# Port_Controller.net
KiCad netlist of a schematic drawn in Altium Designer
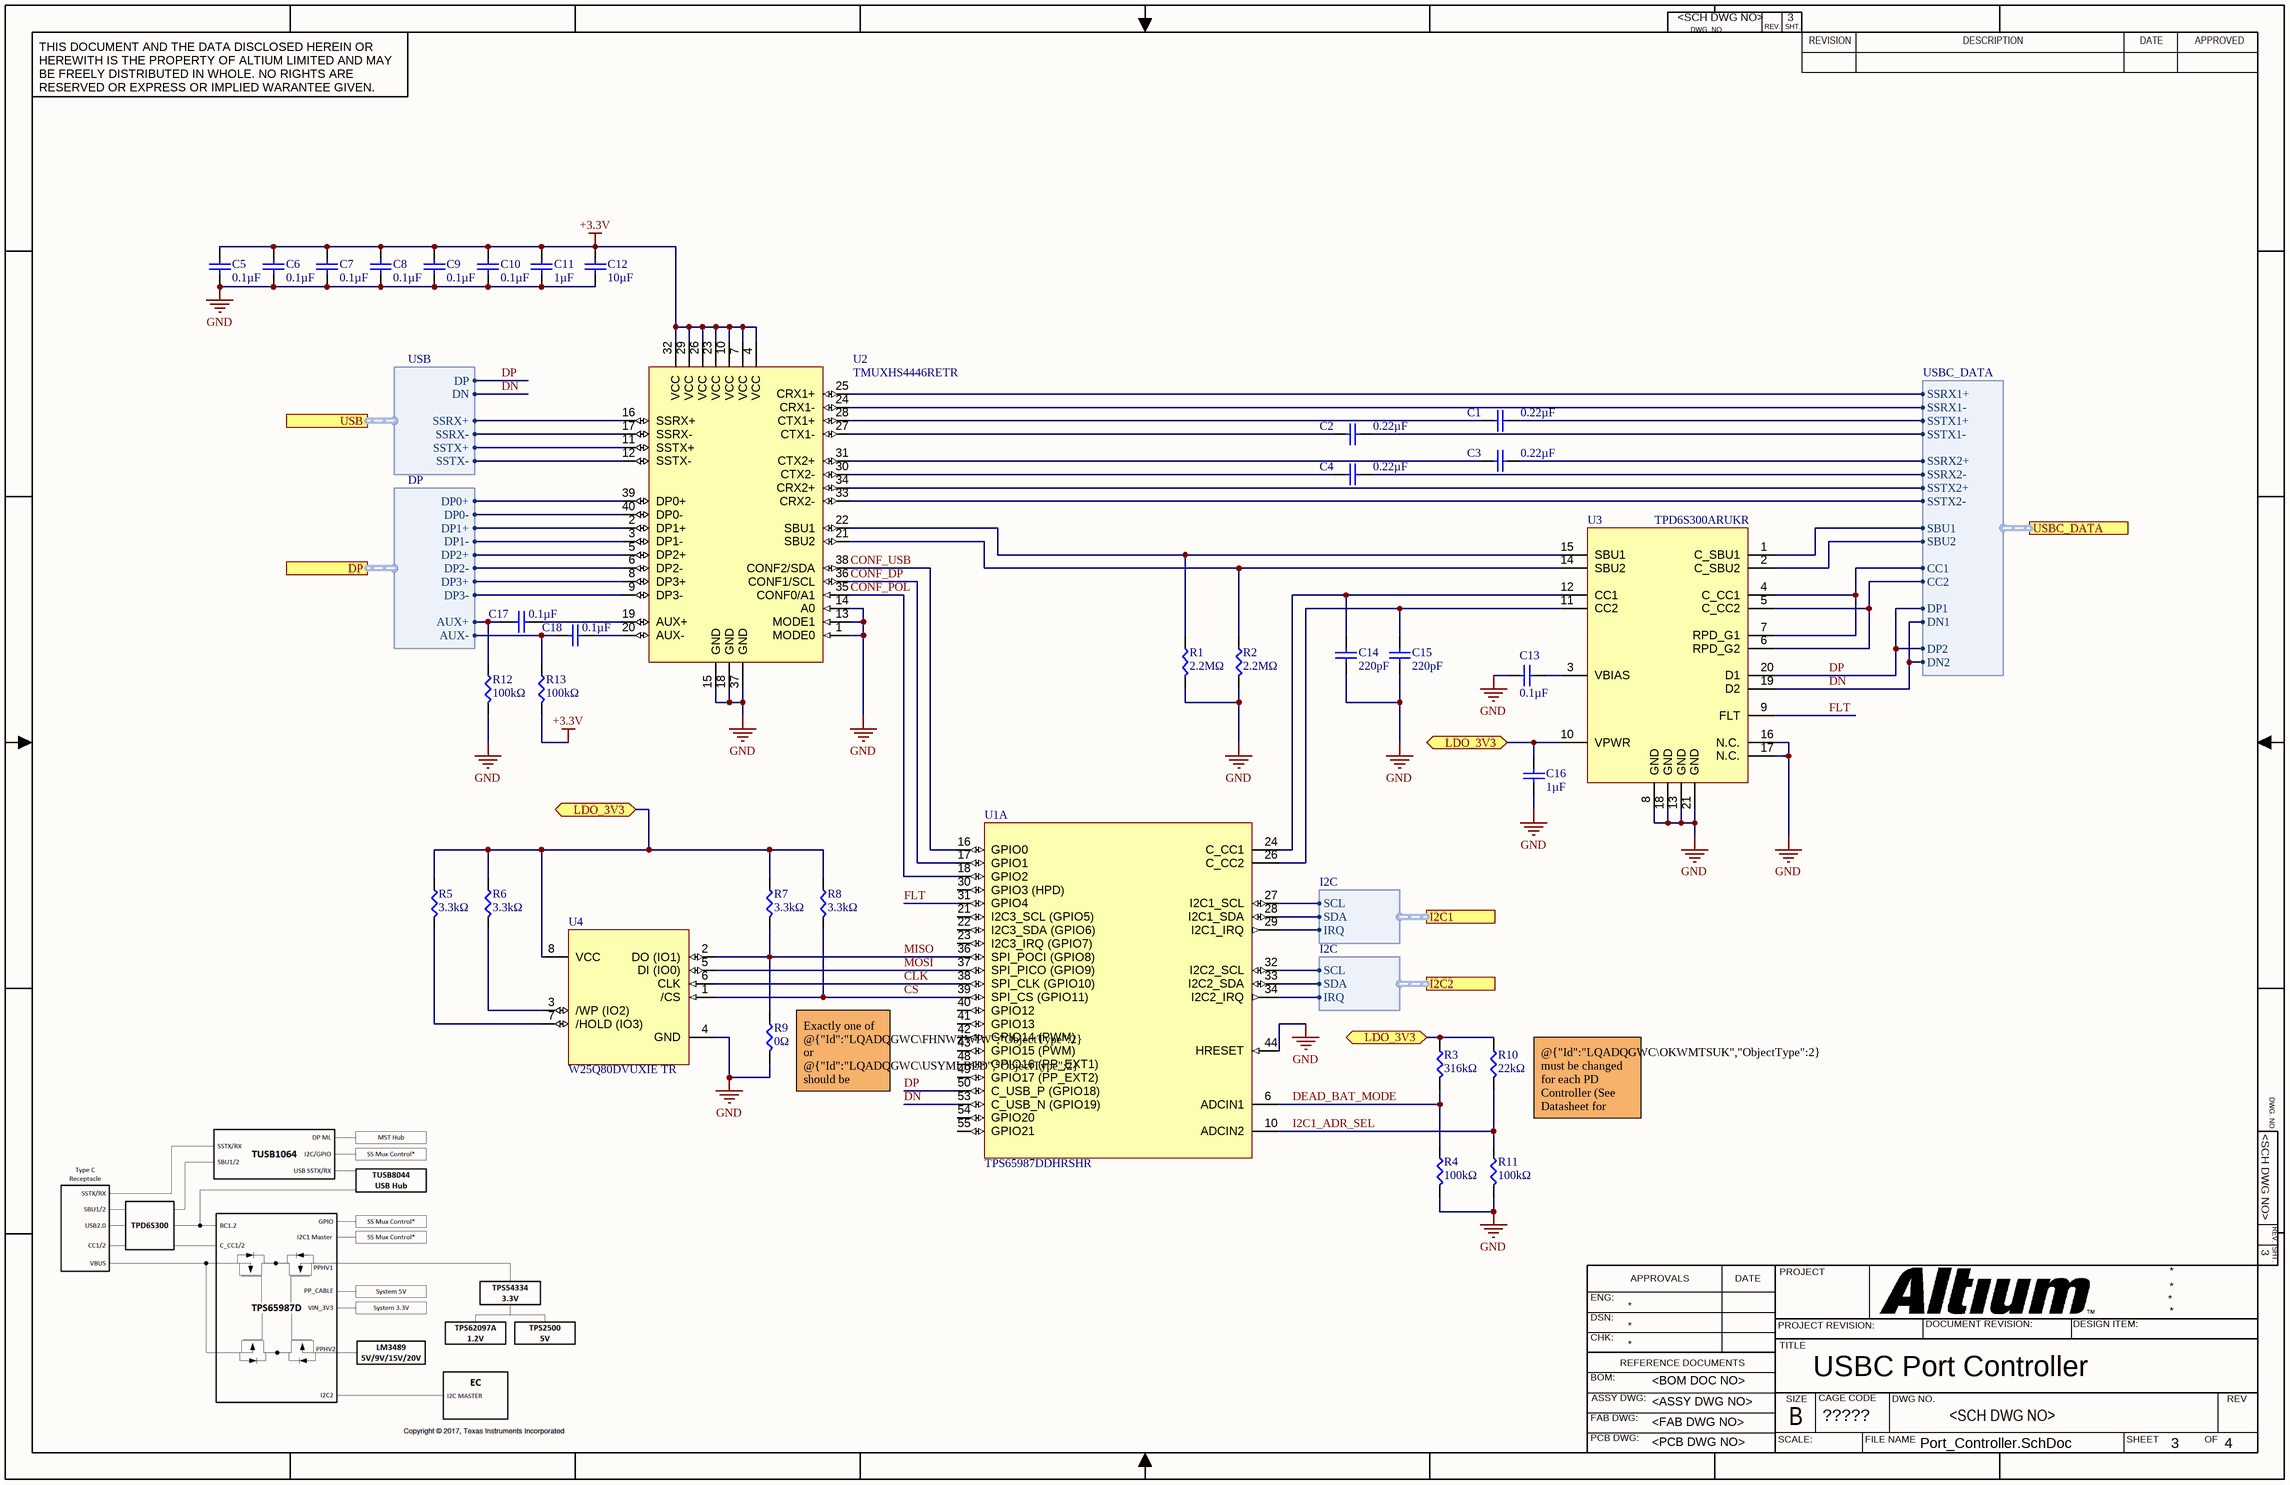
[diagram p0: Port_Controller.SchDoc]

(export (version "E")
  (design (tool "Eeschema 10.0.6"))
  (components
    (comp (ref "C1")
      (value "0.22µF")
      (footprint "CAP0402")
      (description "0.22 µF ±10% 50V Ceramic Capacitor X5R 0402 (1005 Metric)")
      (fields (field (name "VOLTAGE") "50V") (field (name "Comment") "UMK105BJ224KV-F"))
      (libsource (lib "Schlib1") (part "UMK105BJ224KV-F"))
    )
    (comp (ref "C2")
      (value "0.22µF")
      (footprint "CAP0402")
      (description "0.22 µF ±10% 50V Ceramic Capacitor X5R 0402 (1005 Metric)")
      (fields (field (name "VOLTAGE") "50V") (field (name "Comment") "UMK105BJ224KV-F"))
      (libsource (lib "Schlib1") (part "UMK105BJ224KV-F"))
    )
    (comp (ref "C3")
      (value "0.22µF")
      (footprint "CAP0402")
      (description "0.22 µF ±10% 50V Ceramic Capacitor X5R 0402 (1005 Metric)")
      (fields (field (name "VOLTAGE") "50V") (field (name "Comment") "UMK105BJ224KV-F"))
      (libsource (lib "Schlib1") (part "UMK105BJ224KV-F"))
    )
    (comp (ref "C4")
      (value "0.22µF")
      (footprint "CAP0402")
      (description "0.22 µF ±10% 50V Ceramic Capacitor X5R 0402 (1005 Metric)")
      (fields (field (name "VOLTAGE") "50V") (field (name "Comment") "UMK105BJ224KV-F"))
      (libsource (lib "Schlib1") (part "UMK105BJ224KV-F"))
    )
    (comp (ref "C5")
      (value "0.1µF")
      (footprint "CAP0402")
      (description "0.1 µF ±10% 50V Ceramic Capacitor X5R 0402 (1005 Metric)")
      (fields (field (name "VOLTAGE") "50V") (field (name "Comment") "CC0402KRX5R9BB104"))
      (libsource (lib "Schlib1") (part "CC0402KRX5R9BB104"))
    )
    (comp (ref "C6")
      (value "0.1µF")
      (footprint "CAP0402")
      (description "0.1 µF ±10% 50V Ceramic Capacitor X5R 0402 (1005 Metric)")
      (fields (field (name "VOLTAGE") "50V") (field (name "Comment") "CC0402KRX5R9BB104"))
      (libsource (lib "Schlib1") (part "CC0402KRX5R9BB104"))
    )
    (comp (ref "C7")
      (value "0.1µF")
      (footprint "CAP0402")
      (description "0.1 µF ±10% 50V Ceramic Capacitor X5R 0402 (1005 Metric)")
      (fields (field (name "VOLTAGE") "50V") (field (name "Comment") "CC0402KRX5R9BB104"))
      (libsource (lib "Schlib1") (part "CC0402KRX5R9BB104"))
    )
    (comp (ref "C8")
      (value "0.1µF")
      (footprint "CAP0402")
      (description "0.1 µF ±10% 50V Ceramic Capacitor X5R 0402 (1005 Metric)")
      (fields (field (name "VOLTAGE") "50V") (field (name "Comment") "CC0402KRX5R9BB104"))
      (libsource (lib "Schlib1") (part "CC0402KRX5R9BB104"))
    )
    (comp (ref "C9")
      (value "0.1µF")
      (footprint "CAP0402")
      (description "0.1 µF ±10% 50V Ceramic Capacitor X5R 0402 (1005 Metric)")
      (fields (field (name "VOLTAGE") "50V") (field (name "Comment") "CC0402KRX5R9BB104"))
      (libsource (lib "Schlib1") (part "CC0402KRX5R9BB104"))
    )
    (comp (ref "C10")
      (value "0.1µF")
      (footprint "CAP0402")
      (description "0.1 µF ±10% 50V Ceramic Capacitor X5R 0402 (1005 Metric)")
      (fields (field (name "VOLTAGE") "50V") (field (name "Comment") "CC0402KRX5R9BB104"))
      (libsource (lib "Schlib1") (part "CC0402KRX5R9BB104"))
    )
    (comp (ref "C11")
      (value "1µF")
      (footprint "CAP0402")
      (description "1 µF ±10% 16V Ceramic Capacitor X5R 0402 (1005 Metric)")
      (fields (field (name "VOLTAGE") "16V") (field (name "Comment") "CL05A105KO5NNNC"))
      (libsource (lib "Schlib1") (part "CL05A105KO5NNNC"))
    )
    (comp (ref "C12")
      (value "10µF")
      (footprint "CAP0402")
      (description "10 µF ±20% 6.3V Ceramic Capacitor X5R 0402 (1005 Metric)")
      (fields (field (name "VOLTAGE") "6.3V") (field (name "Comment") "CL05A106MQ5NUNC"))
      (libsource (lib "Schlib1") (part "CL05A106MQ5NUNC"))
    )
    (comp (ref "C13")
      (value "0.1µF")
      (footprint "CAP0402")
      (description "0.1 µF ±10% 50V Ceramic Capacitor X5R 0402 (1005 Metric)")
      (fields (field (name "VOLTAGE") "50V") (field (name "Comment") "CC0402KRX5R9BB104"))
      (libsource (lib "Schlib1") (part "CC0402KRX5R9BB104"))
    )
    (comp (ref "C14")
      (value "220pF")
      (footprint "CAP0402")
      (description "220 pF ±5% 50V Ceramic Capacitor C0G, NP0 0402 (1005 Metric)")
      (fields (field (name "VOLTAGE") "50V") (field (name "Comment") "GRM1555C1H221JA01D"))
      (libsource (lib "Schlib1") (part "GRM1555C1H221JA01D"))
    )
    (comp (ref "C15")
      (value "220pF")
      (footprint "CAP0402")
      (description "220 pF ±5% 50V Ceramic Capacitor C0G, NP0 0402 (1005 Metric)")
      (fields (field (name "VOLTAGE") "50V") (field (name "Comment") "GRM1555C1H221JA01D"))
      (libsource (lib "Schlib1") (part "GRM1555C1H221JA01D"))
    )
    (comp (ref "C16")
      (value "1µF")
      (footprint "CAP0402")
      (description "1 µF ±10% 16V Ceramic Capacitor X5R 0402 (1005 Metric)")
      (fields (field (name "VOLTAGE") "16V") (field (name "Comment") "CL05A105KO5NNNC"))
      (libsource (lib "Schlib1") (part "CL05A105KO5NNNC"))
    )
    (comp (ref "C17")
      (value "0.1µF")
      (footprint "CAP0402")
      (description "0.1 µF ±10% 50V Ceramic Capacitor X5R 0402 (1005 Metric)")
      (fields (field (name "VOLTAGE") "50V") (field (name "Comment") "CC0402KRX5R9BB104"))
      (libsource (lib "Schlib1") (part "CC0402KRX5R9BB104"))
    )
    (comp (ref "C18")
      (value "0.1µF")
      (footprint "CAP0402")
      (description "0.1 µF ±10% 50V Ceramic Capacitor X5R 0402 (1005 Metric)")
      (fields (field (name "VOLTAGE") "50V") (field (name "Comment") "CC0402KRX5R9BB104"))
      (libsource (lib "Schlib1") (part "CC0402KRX5R9BB104"))
    )
    (comp (ref "R1")
      (value "2.2MΩ")
      (footprint "RES0402")
      (description "2.2 MOhms ±1% 0.063W, 1/16W Chip Resistor 0402 (1005 Metric) Moisture Resistant Thick Film")
      (fields (field (name "Comment") "RC0402FR-072M2L"))
      (libsource (lib "Schlib1") (part "RC0402FR-072M2L"))
    )
    (comp (ref "R2")
      (value "2.2MΩ")
      (footprint "RES0402")
      (description "2.2 MOhms ±1% 0.063W, 1/16W Chip Resistor 0402 (1005 Metric) Moisture Resistant Thick Film")
      (fields (field (name "Comment") "RC0402FR-072M2L"))
      (libsource (lib "Schlib1") (part "RC0402FR-072M2L"))
    )
    (comp (ref "R3")
      (value "316kΩ")
      (footprint "RES0402")
      (description "316 kOhms ±1% 0.1W, 1/10W Chip Resistor 0402 (1005 Metric) Automotive AEC-Q200 Thick Film")
      (fields (field (name "Comment") "CRCW0402316KFKED"))
      (libsource (lib "Schlib1") (part "CRCW0402316KFKED"))
    )
    (comp (ref "R4")
      (value "100kΩ")
      (footprint "RES0402")
      (description "100 kOhms ±1% 0.1W, 1/10W Chip Resistor 0402 (1005 Metric) Automotive AEC-Q200 Thick Film")
      (fields (field (name "Comment") "ERJ-2RKF1003X"))
      (libsource (lib "Schlib1") (part "ERJ-2RKF1003X"))
    )
    (comp (ref "R5")
      (value "3.3kΩ")
      (footprint "RES0402")
      (description "3.3 kOhms ±0.1% 0.063W, 1/16W Chip Resistor 0402 (1005 Metric) Automotive AEC-Q200 Thin Film")
      (fields (field (name "Comment") "ERA-2AEB332X"))
      (libsource (lib "Schlib1") (part "ERA-2AEB332X"))
    )
    (comp (ref "R6")
      (value "3.3kΩ")
      (footprint "RES0402")
      (description "3.3 kOhms ±0.1% 0.063W, 1/16W Chip Resistor 0402 (1005 Metric) Automotive AEC-Q200 Thin Film")
      (fields (field (name "Comment") "ERA-2AEB332X"))
      (libsource (lib "Schlib1") (part "ERA-2AEB332X"))
    )
    (comp (ref "R7")
      (value "3.3kΩ")
      (footprint "RES0402")
      (description "3.3 kOhms ±0.1% 0.063W, 1/16W Chip Resistor 0402 (1005 Metric) Automotive AEC-Q200 Thin Film")
      (fields (field (name "Comment") "ERA-2AEB332X"))
      (libsource (lib "Schlib1") (part "ERA-2AEB332X"))
    )
    (comp (ref "R8")
      (value "3.3kΩ")
      (footprint "RES0402")
      (description "3.3 kOhms ±0.1% 0.063W, 1/16W Chip Resistor 0402 (1005 Metric) Automotive AEC-Q200 Thin Film")
      (fields (field (name "Comment") "ERA-2AEB332X"))
      (libsource (lib "Schlib1") (part "ERA-2AEB332X"))
    )
    (comp (ref "R9")
      (value "0Ω")
      (footprint "RES0402")
      (description "0 Ohms Jumper Chip Resistor 0402 (1005 Metric) Moisture Resistant Thick Film")
      (fields (field (name "Comment") "RC0402JR-070RL"))
      (libsource (lib "Schlib1") (part "RC0402JR-070RL"))
    )
    (comp (ref "R10")
      (value "22kΩ")
      (footprint "RES0402")
      (description "22 kOhms ±1% 0.1W, 1/10W Chip Resistor 0402 (1005 Metric) Automotive AEC-Q200 Thick Film")
      (fields (field (name "Comment") "ERJ-2RKF2202X"))
      (libsource (lib "Schlib1") (part "ERJ-2RKF2202X"))
    )
    (comp (ref "R11")
      (value "100kΩ")
      (footprint "RES0402")
      (description "100 kOhms ±1% 0.1W, 1/10W Chip Resistor 0402 (1005 Metric) Automotive AEC-Q200 Thick Film")
      (fields (field (name "Comment") "ERJ-2RKF1003X"))
      (libsource (lib "Schlib1") (part "ERJ-2RKF1003X"))
    )
    (comp (ref "R12")
      (value "100kΩ")
      (footprint "RES0402")
      (description "100 kOhms ±1% 0.1W, 1/10W Chip Resistor 0402 (1005 Metric) Automotive AEC-Q200 Thick Film")
      (fields (field (name "Comment") "ERJ-2RKF1003X"))
      (libsource (lib "Schlib1") (part "ERJ-2RKF1003X"))
    )
    (comp (ref "R13")
      (value "100kΩ")
      (footprint "RES0402")
      (description "100 kOhms ±1% 0.1W, 1/10W Chip Resistor 0402 (1005 Metric) Automotive AEC-Q200 Thick Film")
      (fields (field (name "Comment") "ERJ-2RKF1003X"))
      (libsource (lib "Schlib1") (part "ERJ-2RKF1003X"))
    )
    (comp (ref "U1")
      (value "TPS65987DDHRSHR")
      (footprint "56-VQFN (7x7)")
      (description "USB, Type-C Controller PMIC 56-VQFN (7x7)")
      (fields (field (name "MANUFACTURER") "Texas Instruments"))
      (libsource (lib "Schlib1") (part "TPS65987DDHRSHR"))
    )
    (comp (ref "U2")
      (value "TMUXHS4446RETR")
      (description "4 Circuit IC Switch 4:4 7Ohm (Typ) 40-WQFN (6x3)")
      (fields (field (name "MANUFACTURER") "Texas Instruments"))
      (libsource (lib "Schlib1") (part "TMUXHS4446RETR"))
    )
    (comp (ref "U3")
      (value "TPD6S300ARUKR")
      (description "Overvoltage/Surge Protection IC 8V Internal Switch 20-WQFN (3x3)")
      (fields (field (name "MANUFACTURER") "Texas Instruments"))
      (libsource (lib "Schlib1") (part "TPD6S300ARUKR"))
    )
    (comp (ref "U4")
      (value "W25Q80DVUXIE TR")
      (description "FLASH - NOR Memory IC 8Mbit SPI - Quad I/O 104 MHz 8-USON (2x3)")
      (fields (field (name "MANUFACTURER") "Winbond Electronics"))
      (libsource (lib "Schlib1") (part "W25Q80DVUXIE TR"))
    )
  )
  (nets
    (net (code "4") (name "+3.3V") (class "Default")
      (node (ref "C10") (pin "2") (pinfunction "2_2") (pintype "passive"))
      (node (ref "C11") (pin "2") (pinfunction "2_2") (pintype "passive"))
      (node (ref "C12") (pin "2") (pinfunction "2_2") (pintype "passive"))
      (node (ref "C5") (pin "2") (pinfunction "2_2") (pintype "passive"))
      (node (ref "C6") (pin "2") (pinfunction "2_2") (pintype "passive"))
      (node (ref "C7") (pin "2") (pinfunction "2_2") (pintype "passive"))
      (node (ref "C8") (pin "2") (pinfunction "2_2") (pintype "passive"))
      (node (ref "C9") (pin "2") (pinfunction "2_2") (pintype "passive"))
      (node (ref "R13") (pin "1") (pinfunction "1_1") (pintype "passive"))
      (node (ref "U2") (pin "10") (pinfunction "VCC_10") (pintype "passive"))
      (node (ref "U2") (pin "23") (pinfunction "VCC_23") (pintype "passive"))
      (node (ref "U2") (pin "26") (pinfunction "VCC_26") (pintype "passive"))
      (node (ref "U2") (pin "29") (pinfunction "VCC_29") (pintype "passive"))
      (node (ref "U2") (pin "32") (pinfunction "VCC_32") (pintype "passive"))
      (node (ref "U2") (pin "4") (pinfunction "VCC_4") (pintype "passive"))
      (node (ref "U2") (pin "7") (pinfunction "VCC_7") (pintype "passive"))
    )
    (net (code "5") (name "/AUX+") (class "Default")
      (node (ref "C17") (pin "1") (pinfunction "1_1") (pintype "passive"))
      (node (ref "R12") (pin "2") (pinfunction "2_2") (pintype "passive"))
    )
    (net (code "6") (name "/AUX-") (class "Default")
      (node (ref "C18") (pin "1") (pinfunction "1_1") (pintype "passive"))
      (node (ref "R13") (pin "2") (pinfunction "2_2") (pintype "passive"))
    )
    (net (code "7") (name "/CC1") (class "Default")
      (node (ref "U3") (pin "4") (pinfunction "C_CC1_4") (pintype "passive"))
      (node (ref "U3") (pin "7") (pinfunction "RPD_G1_7") (pintype "passive"))
    )
    (net (code "8") (name "/CC2") (class "Default")
      (node (ref "U3") (pin "5") (pinfunction "C_CC2_5") (pintype "passive"))
      (node (ref "U3") (pin "6") (pinfunction "RPD_G2_6") (pintype "passive"))
    )
    (net (code "9") (name "/CLK") (class "Default")
      (node (ref "U1") (pin "38") (pinfunction "SPI_CLK_(GPIO10)_38") (pintype "bidirectional"))
      (node (ref "U4") (pin "6") (pinfunction "CLK_6") (pintype "input"))
    )
    (net (code "10") (name "/CONF_DP") (class "Default")
      (node (ref "U1") (pin "17") (pinfunction "GPIO1_17") (pintype "bidirectional"))
      (node (ref "U2") (pin "36") (pinfunction "CONF1/SCL_36") (pintype "bidirectional"))
    )
    (net (code "11") (name "/CONF_POL") (class "Default")
      (node (ref "U1") (pin "18") (pinfunction "GPIO2_18") (pintype "bidirectional"))
      (node (ref "U2") (pin "35") (pinfunction "CONF0/A1_35") (pintype "input"))
    )
    (net (code "12") (name "/CONF_USB") (class "Default")
      (node (ref "U1") (pin "16") (pinfunction "GPIO0_16") (pintype "bidirectional"))
      (node (ref "U2") (pin "38") (pinfunction "CONF2/SDA_38") (pintype "bidirectional"))
    )
    (net (code "13") (name "/CS") (class "Default")
      (node (ref "R8") (pin "1") (pinfunction "1_1") (pintype "passive"))
      (node (ref "U1") (pin "39") (pinfunction "SPI_CS_(GPIO11)_39") (pintype "bidirectional"))
      (node (ref "U4") (pin "1") (pinfunction "/CS_1") (pintype "input"))
    )
    (net (code "14") (name "/DEAD_BAT_MODE") (class "Default")
      (node (ref "R3") (pin "1") (pinfunction "1_1") (pintype "passive"))
      (node (ref "R4") (pin "2") (pinfunction "2_2") (pintype "passive"))
      (node (ref "U1") (pin "6") (pinfunction "ADCIN1_6") (pintype "passive"))
    )
    (net (code "15") (name "/DN") (class "Default")
      (node (ref "U1") (pin "53") (pinfunction "C_USB_N_(GPIO19)_53") (pintype "bidirectional"))
      (node (ref "U3") (pin "19") (pinfunction "D2_19") (pintype "passive"))
    )
    (net (code "16") (name "/DP") (class "Default")
      (node (ref "U1") (pin "50") (pinfunction "C_USB_P_(GPIO18)_50") (pintype "bidirectional"))
      (node (ref "U3") (pin "20") (pinfunction "D1_20") (pintype "passive"))
    )
    (net (code "17") (name "/DP0+") (class "Default")
      (node (ref "U2") (pin "39") (pinfunction "DP0+_39") (pintype "bidirectional"))
    )
    (net (code "18") (name "/DP0-") (class "Default")
      (node (ref "U2") (pin "40") (pinfunction "DP0-_40") (pintype "bidirectional"))
    )
    (net (code "19") (name "/DP1+") (class "Default")
      (node (ref "U2") (pin "2") (pinfunction "DP1+_2") (pintype "bidirectional"))
    )
    (net (code "20") (name "/DP1-") (class "Default")
      (node (ref "U2") (pin "3") (pinfunction "DP1-_3") (pintype "bidirectional"))
    )
    (net (code "21") (name "/DP2+") (class "Default")
      (node (ref "U2") (pin "5") (pinfunction "DP2+_5") (pintype "bidirectional"))
    )
    (net (code "22") (name "/DP2-") (class "Default")
      (node (ref "U2") (pin "6") (pinfunction "DP2-_6") (pintype "bidirectional"))
    )
    (net (code "23") (name "/DP3+") (class "Default")
      (node (ref "U2") (pin "8") (pinfunction "DP3+_8") (pintype "bidirectional"))
    )
    (net (code "24") (name "/DP3-") (class "Default")
      (node (ref "U2") (pin "9") (pinfunction "DP3-_9") (pintype "bidirectional"))
    )
    (net (code "25") (name "/FLT") (class "Default")
      (node (ref "U1") (pin "31") (pinfunction "GPIO4_31") (pintype "bidirectional"))
      (node (ref "U3") (pin "9") (pinfunction "FLT_9") (pintype "passive"))
    )
    (net (code "26") (name "/I2C1_ADR_SEL") (class "Default")
      (node (ref "R10") (pin "1") (pinfunction "1_1") (pintype "passive"))
      (node (ref "R11") (pin "2") (pinfunction "2_2") (pintype "passive"))
      (node (ref "U1") (pin "10") (pinfunction "ADCIN2_10") (pintype "passive"))
    )
    (net (code "27") (name "/LDO_3V3") (class "Default")
      (node (ref "C16") (pin "2") (pinfunction "2_2") (pintype "passive"))
      (node (ref "R10") (pin "2") (pinfunction "2_2") (pintype "passive"))
      (node (ref "R3") (pin "2") (pinfunction "2_2") (pintype "passive"))
      (node (ref "R5") (pin "2") (pinfunction "2_2") (pintype "passive"))
      (node (ref "R6") (pin "2") (pinfunction "2_2") (pintype "passive"))
      (node (ref "R7") (pin "2") (pinfunction "2_2") (pintype "passive"))
      (node (ref "R8") (pin "2") (pinfunction "2_2") (pintype "passive"))
      (node (ref "U3") (pin "10") (pinfunction "VPWR_10") (pintype "passive"))
      (node (ref "U4") (pin "8") (pinfunction "VCC_8") (pintype "passive"))
    )
    (net (code "28") (name "/MISO") (class "Default")
      (node (ref "R7") (pin "1") (pinfunction "1_1") (pintype "passive"))
      (node (ref "R9") (pin "2") (pinfunction "2_2") (pintype "passive"))
      (node (ref "U1") (pin "36") (pinfunction "SPI_POCI_(GPIO8)_36") (pintype "bidirectional"))
      (node (ref "U4") (pin "2") (pinfunction "DO_(IO1)_2") (pintype "bidirectional"))
    )
    (net (code "29") (name "/MOSI") (class "Default")
      (node (ref "U1") (pin "37") (pinfunction "SPI_PICO_(GPIO9)_37") (pintype "bidirectional"))
      (node (ref "U4") (pin "5") (pinfunction "DI_(IO0)_5") (pintype "bidirectional"))
    )
    (net (code "30") (name "/SBU1") (class "Default")
      (node (ref "U3") (pin "1") (pinfunction "C_SBU1_1") (pintype "passive"))
    )
    (net (code "31") (name "/SBU2") (class "Default")
      (node (ref "U3") (pin "2") (pinfunction "C_SBU2_2") (pintype "passive"))
    )
    (net (code "32") (name "/SSRX+") (class "Default")
      (node (ref "U2") (pin "16") (pinfunction "SSRX+_16") (pintype "bidirectional"))
    )
    (net (code "33") (name "/SSRX-") (class "Default")
      (node (ref "U2") (pin "17") (pinfunction "SSRX-_17") (pintype "bidirectional"))
    )
    (net (code "34") (name "/SSRX1+") (class "Default")
      (node (ref "U2") (pin "25") (pinfunction "CRX1+_25") (pintype "bidirectional"))
    )
    (net (code "35") (name "/SSRX1-") (class "Default")
      (node (ref "U2") (pin "24") (pinfunction "CRX1-_24") (pintype "bidirectional"))
    )
    (net (code "36") (name "/SSRX2+") (class "Default")
      (node (ref "C3") (pin "2") (pinfunction "2_2") (pintype "passive"))
    )
    (net (code "37") (name "/SSRX2-") (class "Default")
      (node (ref "C4") (pin "2") (pinfunction "2_2") (pintype "passive"))
    )
    (net (code "38") (name "/SSTX+") (class "Default")
      (node (ref "U2") (pin "11") (pinfunction "SSTX+_11") (pintype "bidirectional"))
    )
    (net (code "39") (name "/SSTX-") (class "Default")
      (node (ref "U2") (pin "12") (pinfunction "SSTX-_12") (pintype "bidirectional"))
    )
    (net (code "40") (name "/SSTX1+") (class "Default")
      (node (ref "C1") (pin "2") (pinfunction "2_2") (pintype "passive"))
    )
    (net (code "41") (name "/SSTX1-") (class "Default")
      (node (ref "C2") (pin "2") (pinfunction "2_2") (pintype "passive"))
    )
    (net (code "42") (name "/SSTX2+") (class "Default")
      (node (ref "U2") (pin "34") (pinfunction "CRX2+_34") (pintype "bidirectional"))
    )
    (net (code "43") (name "/SSTX2-") (class "Default")
      (node (ref "U2") (pin "33") (pinfunction "CRX2-_33") (pintype "bidirectional"))
    )
    (net (code "48") (name "GND") (class "Default")
      (node (ref "C10") (pin "1") (pinfunction "1_1") (pintype "passive"))
      (node (ref "C11") (pin "1") (pinfunction "1_1") (pintype "passive"))
      (node (ref "C12") (pin "1") (pinfunction "1_1") (pintype "passive"))
      (node (ref "C13") (pin "1") (pinfunction "1_1") (pintype "passive"))
      (node (ref "C14") (pin "1") (pinfunction "1_1") (pintype "passive"))
      (node (ref "C15") (pin "1") (pinfunction "1_1") (pintype "passive"))
      (node (ref "C16") (pin "1") (pinfunction "1_1") (pintype "passive"))
      (node (ref "C5") (pin "1") (pinfunction "1_1") (pintype "passive"))
      (node (ref "C6") (pin "1") (pinfunction "1_1") (pintype "passive"))
      (node (ref "C7") (pin "1") (pinfunction "1_1") (pintype "passive"))
      (node (ref "C8") (pin "1") (pinfunction "1_1") (pintype "passive"))
      (node (ref "C9") (pin "1") (pinfunction "1_1") (pintype "passive"))
      (node (ref "R1") (pin "1") (pinfunction "1_1") (pintype "passive"))
      (node (ref "R11") (pin "1") (pinfunction "1_1") (pintype "passive"))
      (node (ref "R12") (pin "1") (pinfunction "1_1") (pintype "passive"))
      (node (ref "R2") (pin "1") (pinfunction "1_1") (pintype "passive"))
      (node (ref "R4") (pin "1") (pinfunction "1_1") (pintype "passive"))
      (node (ref "R9") (pin "1") (pinfunction "1_1") (pintype "passive"))
      (node (ref "U1") (pin "44") (pinfunction "HRESET_44") (pintype "input"))
      (node (ref "U2") (pin "1") (pinfunction "MODE0_1") (pintype "input"))
      (node (ref "U2") (pin "13") (pinfunction "MODE1_13") (pintype "input"))
      (node (ref "U2") (pin "14") (pinfunction "A0_14") (pintype "input"))
      (node (ref "U2") (pin "15") (pinfunction "GND_15") (pintype "passive"))
      (node (ref "U2") (pin "18") (pinfunction "GND_18") (pintype "passive"))
      (node (ref "U2") (pin "37") (pinfunction "GND_37") (pintype "passive"))
      (node (ref "U3") (pin "13") (pinfunction "GND_13") (pintype "passive"))
      (node (ref "U3") (pin "16") (pinfunction "N.C._16") (pintype "passive"))
      (node (ref "U3") (pin "17") (pinfunction "N.C._17") (pintype "passive"))
      (node (ref "U3") (pin "18") (pinfunction "GND_18") (pintype "passive"))
      (node (ref "U3") (pin "21") (pinfunction "GND_21") (pintype "passive"))
      (node (ref "U3") (pin "8") (pinfunction "GND_8") (pintype "passive"))
      (node (ref "U4") (pin "4") (pinfunction "GND_4") (pintype "passive"))
    )
    (net (code "49") (name "Net-(U1A-C_CC1)") (class "Default")
      (node (ref "C14") (pin "2") (pinfunction "2_2") (pintype "passive"))
      (node (ref "U1") (pin "24") (pinfunction "C_CC1_24") (pintype "passive"))
      (node (ref "U3") (pin "12") (pinfunction "CC1_12") (pintype "passive"))
    )
    (net (code "50") (name "Net-(U1A-C_CC2)") (class "Default")
      (node (ref "C15") (pin "2") (pinfunction "2_2") (pintype "passive"))
      (node (ref "U1") (pin "26") (pinfunction "C_CC2_26") (pintype "passive"))
      (node (ref "U3") (pin "11") (pinfunction "CC2_11") (pintype "passive"))
    )
    (net (code "51") (name "Net-(U2-AUX+)") (class "Default")
      (node (ref "C17") (pin "2") (pinfunction "2_2") (pintype "passive"))
      (node (ref "U2") (pin "19") (pinfunction "AUX+_19") (pintype "bidirectional"))
    )
    (net (code "52") (name "Net-(U2-AUX-)") (class "Default")
      (node (ref "C18") (pin "2") (pinfunction "2_2") (pintype "passive"))
      (node (ref "U2") (pin "20") (pinfunction "AUX-_20") (pintype "bidirectional"))
    )
    (net (code "53") (name "Net-(U2-CTX1+)") (class "Default")
      (node (ref "C1") (pin "1") (pinfunction "1_1") (pintype "passive"))
      (node (ref "U2") (pin "28") (pinfunction "CTX1+_28") (pintype "bidirectional"))
    )
    (net (code "54") (name "Net-(U2-CTX1-)") (class "Default")
      (node (ref "C2") (pin "1") (pinfunction "1_1") (pintype "passive"))
      (node (ref "U2") (pin "27") (pinfunction "CTX1-_27") (pintype "bidirectional"))
    )
    (net (code "55") (name "Net-(U2-CTX2+)") (class "Default")
      (node (ref "C3") (pin "1") (pinfunction "1_1") (pintype "passive"))
      (node (ref "U2") (pin "31") (pinfunction "CTX2+_31") (pintype "bidirectional"))
    )
    (net (code "56") (name "Net-(U2-CTX2-)") (class "Default")
      (node (ref "C4") (pin "1") (pinfunction "1_1") (pintype "passive"))
      (node (ref "U2") (pin "30") (pinfunction "CTX2-_30") (pintype "bidirectional"))
    )
    (net (code "57") (name "Net-(U2-SBU1)") (class "Default")
      (node (ref "R1") (pin "2") (pinfunction "2_2") (pintype "passive"))
      (node (ref "U2") (pin "22") (pinfunction "SBU1_22") (pintype "bidirectional"))
      (node (ref "U3") (pin "15") (pinfunction "SBU1_15") (pintype "passive"))
    )
    (net (code "58") (name "Net-(U2-SBU2)") (class "Default")
      (node (ref "R2") (pin "2") (pinfunction "2_2") (pintype "passive"))
      (node (ref "U2") (pin "21") (pinfunction "SBU2_21") (pintype "bidirectional"))
      (node (ref "U3") (pin "14") (pinfunction "SBU2_14") (pintype "passive"))
    )
    (net (code "59") (name "Net-(U3-VBIAS)") (class "Default")
      (node (ref "C13") (pin "2") (pinfunction "2_2") (pintype "passive"))
      (node (ref "U3") (pin "3") (pinfunction "VBIAS_3") (pintype "passive"))
    )
    (net (code "60") (name "Net-(U4-{slash}HOLD_(IO3))") (class "Default")
      (node (ref "R5") (pin "1") (pinfunction "1_1") (pintype "passive"))
      (node (ref "U4") (pin "7") (pinfunction "/HOLD_(IO3)_7") (pintype "bidirectional"))
    )
    (net (code "61") (name "Net-(U4-{slash}WP_(IO2))") (class "Default")
      (node (ref "R6") (pin "1") (pinfunction "1_1") (pintype "passive"))
      (node (ref "U4") (pin "3") (pinfunction "/WP_(IO2)_3") (pintype "bidirectional"))
    )
    (net (code "62") (name "unconnected-(U1A-GPIO3_(HPD)-Pad30)") (class "Default")
      (node (ref "U1") (pin "30") (pinfunction "GPIO3_(HPD)_30") (pintype "bidirectional"))
    )
    (net (code "63") (name "unconnected-(U1A-GPIO12-Pad40)") (class "Default")
      (node (ref "U1") (pin "40") (pinfunction "GPIO12_40") (pintype "bidirectional"))
    )
    (net (code "64") (name "unconnected-(U1A-GPIO13-Pad41)") (class "Default")
      (node (ref "U1") (pin "41") (pinfunction "GPIO13_41") (pintype "bidirectional"))
    )
    (net (code "65") (name "unconnected-(U1A-GPIO14_(PWM)-Pad42)") (class "Default")
      (node (ref "U1") (pin "42") (pinfunction "GPIO14_(PWM)_42") (pintype "bidirectional"))
    )
    (net (code "66") (name "unconnected-(U1A-GPIO15_(PWM)-Pad43)") (class "Default")
      (node (ref "U1") (pin "43") (pinfunction "GPIO15_(PWM)_43") (pintype "bidirectional"))
    )
    (net (code "67") (name "unconnected-(U1A-GPIO16_(PP_EXT1)-Pad48)") (class "Default")
      (node (ref "U1") (pin "48") (pinfunction "GPIO16_(PP_EXT1)_48") (pintype "bidirectional"))
    )
    (net (code "68") (name "unconnected-(U1A-GPIO17_(PP_EXT2)-Pad49)") (class "Default")
      (node (ref "U1") (pin "49") (pinfunction "GPIO17_(PP_EXT2)_49") (pintype "bidirectional"))
    )
    (net (code "69") (name "unconnected-(U1A-GPIO20-Pad54)") (class "Default")
      (node (ref "U1") (pin "54") (pinfunction "GPIO20_54") (pintype "bidirectional"))
    )
    (net (code "70") (name "unconnected-(U1A-GPIO21-Pad55)") (class "Default")
      (node (ref "U1") (pin "55") (pinfunction "GPIO21_55") (pintype "bidirectional"))
    )
    (net (code "71") (name "unconnected-(U1A-I2C1_IRQ-Pad29)") (class "Default")
      (node (ref "U1") (pin "29") (pinfunction "I2C1_IRQ_29") (pintype "output"))
    )
    (net (code "72") (name "unconnected-(U1A-I2C1_SCL-Pad27)") (class "Default")
      (node (ref "U1") (pin "27") (pinfunction "I2C1_SCL_27") (pintype "bidirectional"))
    )
    (net (code "73") (name "unconnected-(U1A-I2C1_SDA-Pad28)") (class "Default")
      (node (ref "U1") (pin "28") (pinfunction "I2C1_SDA_28") (pintype "bidirectional"))
    )
    (net (code "74") (name "unconnected-(U1A-I2C2_IRQ-Pad34)") (class "Default")
      (node (ref "U1") (pin "34") (pinfunction "I2C2_IRQ_34") (pintype "output"))
    )
    (net (code "75") (name "unconnected-(U1A-I2C2_SCL-Pad32)") (class "Default")
      (node (ref "U1") (pin "32") (pinfunction "I2C2_SCL_32") (pintype "bidirectional"))
    )
    (net (code "76") (name "unconnected-(U1A-I2C2_SDA-Pad33)") (class "Default")
      (node (ref "U1") (pin "33") (pinfunction "I2C2_SDA_33") (pintype "bidirectional"))
    )
    (net (code "77") (name "unconnected-(U1A-I2C3_IRQ_(GPIO7)-Pad23)") (class "Default")
      (node (ref "U1") (pin "23") (pinfunction "I2C3_IRQ_(GPIO7)_23") (pintype "bidirectional"))
    )
    (net (code "78") (name "unconnected-(U1A-I2C3_SCL_(GPIO5)-Pad21)") (class "Default")
      (node (ref "U1") (pin "21") (pinfunction "I2C3_SCL_(GPIO5)_21") (pintype "bidirectional"))
    )
    (net (code "79") (name "unconnected-(U1A-I2C3_SDA_(GPIO6)-Pad22)") (class "Default")
      (node (ref "U1") (pin "22") (pinfunction "I2C3_SDA_(GPIO6)_22") (pintype "bidirectional"))
    )
  )
)
